# PowerBoard.net
KiCad netlist of a schematic drawn in Altium Designer
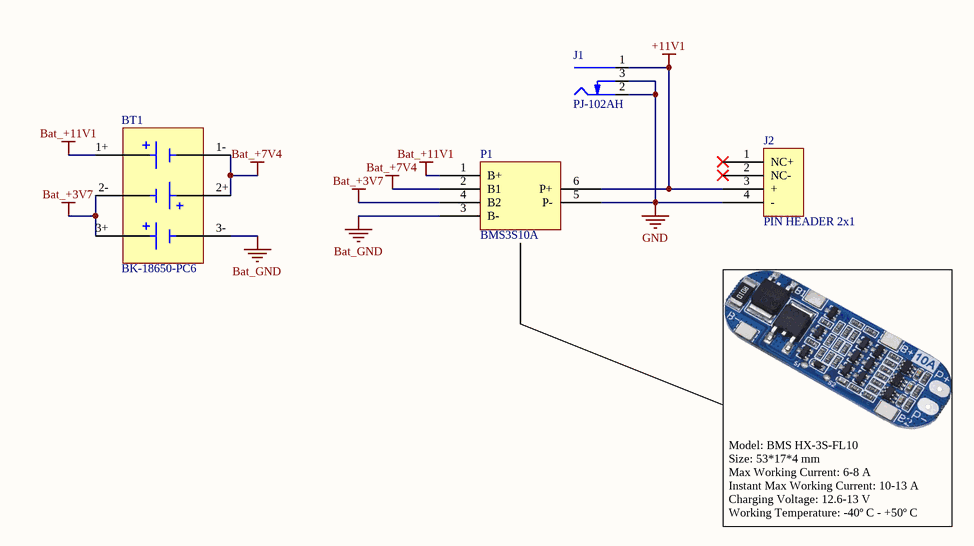
[diagram p0: PowerBoard.SchDoc]

(export (version "E")
  (design (tool "Eeschema 10.0.6"))
  (components
    (comp (ref "BT1")
      (value "BK-18650-PC6")
      (footprint "BAT_BK-18650-PC6")
      (description "Battery Holder _Open_ 18650 3 Cell PC Pin")
      (fields (field (name "MF") "MPD"))
      (libsource (lib "PowerBoard") (part "BK-18650-PC6"))
    )
    (comp (ref "J1")
      (value "PJ-102AH")
      (footprint "CUI PJ-102AH")
      (description "CONN PWR JACK 2X5.5MM SOLDER")
      (fields (field (name "MANUFACTURER") "CUI Devices"))
      (libsource (lib "PowerBoard") (part "PJ-102AH"))
    )
    (comp (ref "J2")
      (value "PIN HEADER 2x1")
      (footprint "M20-9950245")
      (description "M20-9950245 Pin Connector")
      (libsource (lib "PowerBoard") (part "M20-9950245"))
    )
    (comp (ref "P1") (value "BMS3S10A") (footprint "BMS") (libsource (lib "PowerBoard") (part "BMS")))
  )
  (nets
    (net (code "1") (name "+11V1") (class "Default")
      (node (ref "J1") (pin "1") (pinfunction "Centre_1") (pintype "passive"))
      (node (ref "J2") (pin "3") (pinfunction "+_3") (pintype "power_in"))
      (node (ref "P1") (pin "6") (pinfunction "P+_6") (pintype "passive"))
    )
    (net (code "2") (name "Bat_+3V7") (class "Default")
      (node (ref "BT1") (pin "2-") (pinfunction "2-_2-") (pintype "passive"))
      (node (ref "BT1") (pin "3+") (pinfunction "3+_3+") (pintype "passive"))
      (node (ref "P1") (pin "4") (pinfunction "B2_4") (pintype "passive"))
    )
    (net (code "3") (name "Bat_+7V4") (class "Default")
      (node (ref "BT1") (pin "1-") (pinfunction "1-_1-") (pintype "passive"))
      (node (ref "BT1") (pin "2+") (pinfunction "2+_2+") (pintype "passive"))
      (node (ref "P1") (pin "2") (pinfunction "B1_2") (pintype "passive"))
    )
    (net (code "4") (name "Bat_+11V1") (class "Default")
      (node (ref "BT1") (pin "1+") (pinfunction "1+_1+") (pintype "passive"))
      (node (ref "P1") (pin "1") (pinfunction "B+_1") (pintype "passive"))
    )
    (net (code "5") (name "Bat_GND") (class "Default")
      (node (ref "BT1") (pin "3-") (pinfunction "3-_3-") (pintype "passive"))
      (node (ref "P1") (pin "3") (pinfunction "B-_3") (pintype "passive"))
    )
    (net (code "6") (name "GND") (class "Default")
      (node (ref "J1") (pin "2") (pinfunction "Outer_2") (pintype "passive"))
      (node (ref "J1") (pin "3") (pinfunction "SW_3") (pintype "passive"))
      (node (ref "J2") (pin "4") (pinfunction "-_4") (pintype "power_in"))
      (node (ref "P1") (pin "5") (pinfunction "P-_5") (pintype "passive"))
    )
    (net (code "7") (name "unconnected-(J2-NC+-Pad1)") (class "Default")
      (node (ref "J2") (pin "1") (pinfunction "NC+_1") (pintype "power_in+no_connect"))
    )
    (net (code "8") (name "unconnected-(J2-NC--Pad2)") (class "Default")
      (node (ref "J2") (pin "2") (pinfunction "NC-_2") (pintype "power_in+no_connect"))
    )
  )
)
